# DAC_1_0.net
KiCad netlist of a schematic drawn in EAGLE
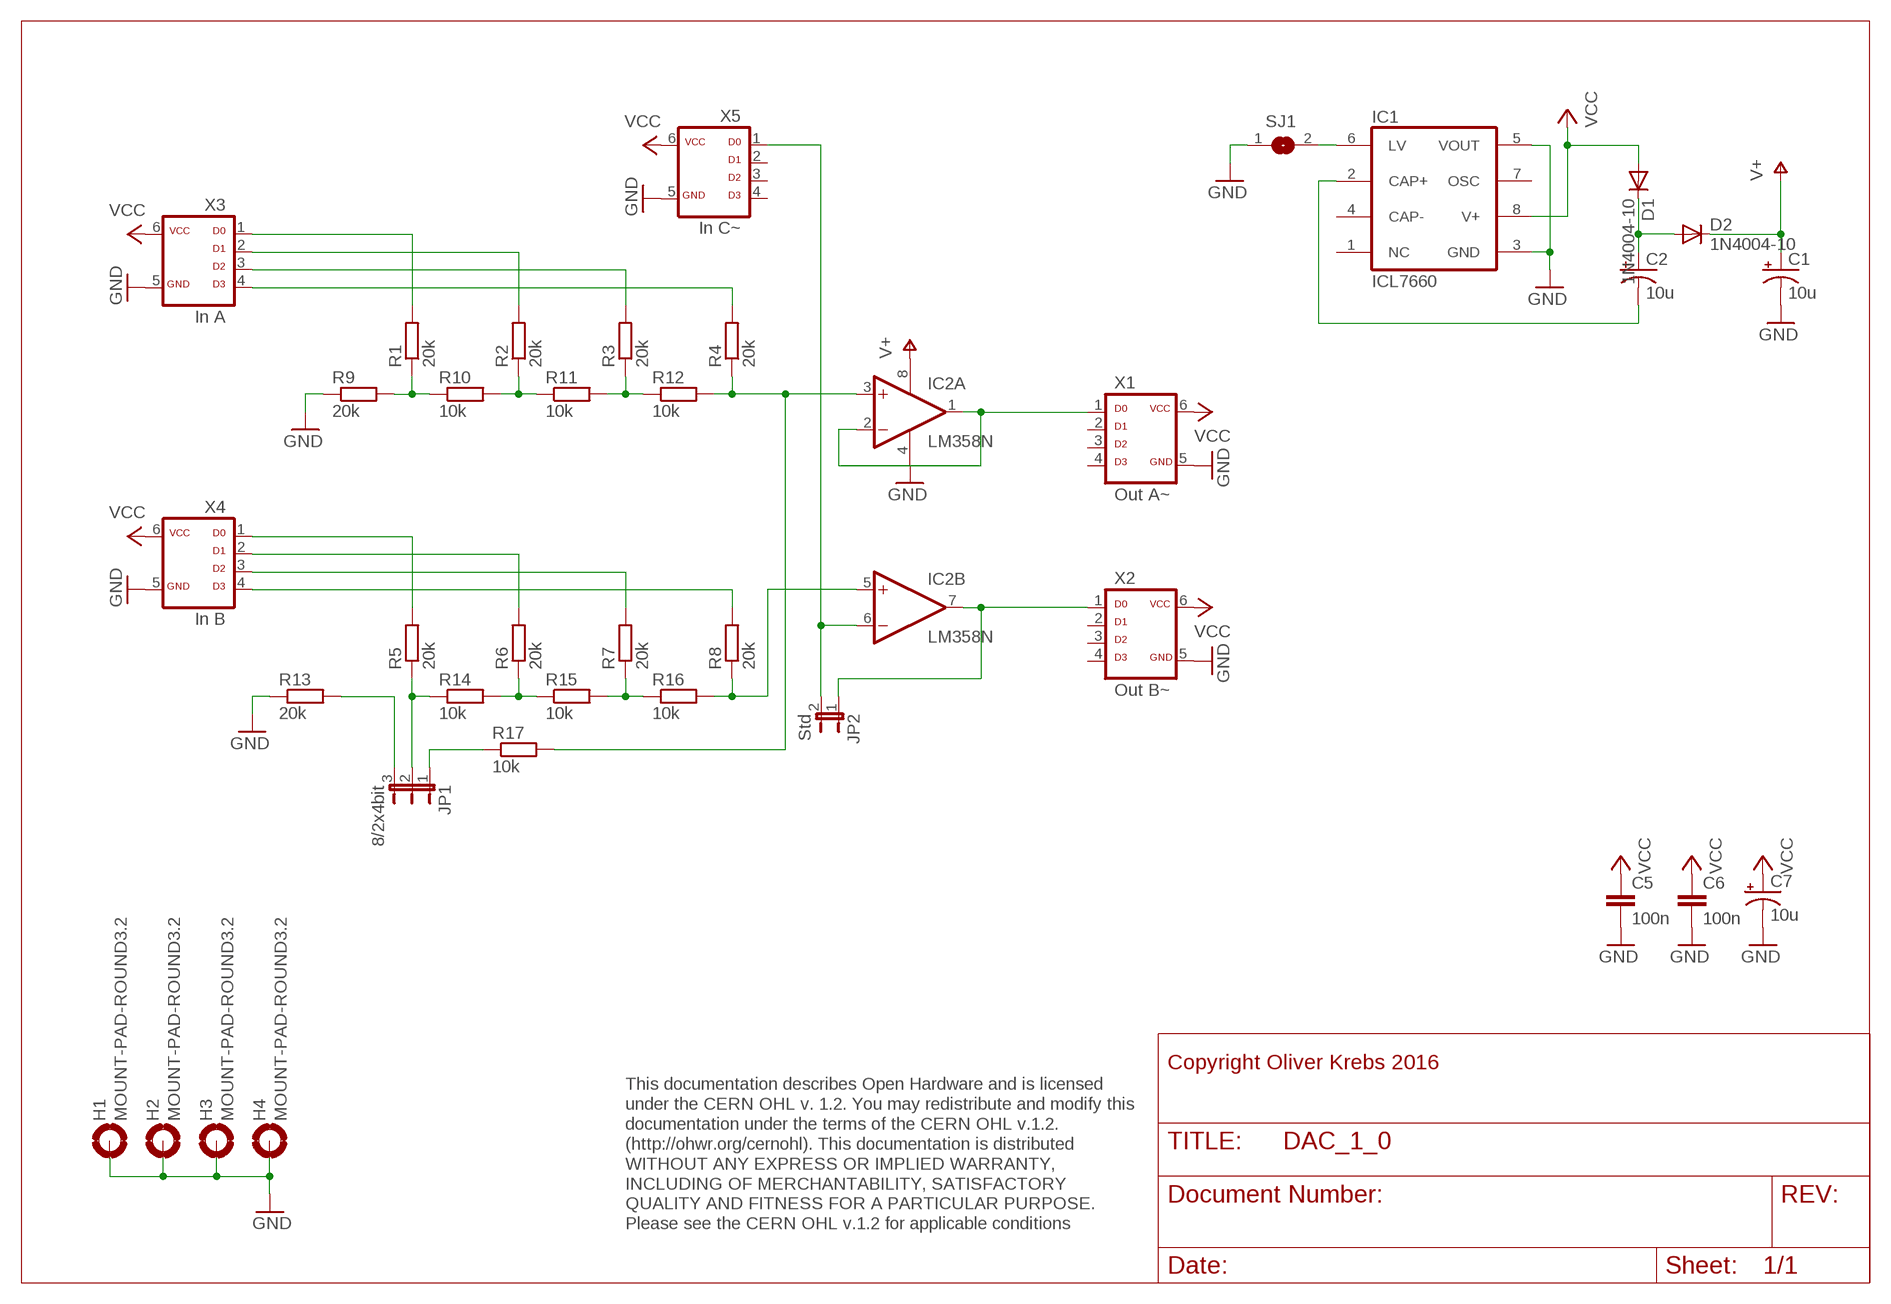
[diagram p0: schematic, sheet 1]

(export (version "E")
  (design (tool "Eeschema 10.0.6"))
  (components
    (comp (ref "C1")
      (value "10u")
      (footprint "eagle-import:CPOL-RADIAL-10UF-25V")
      (libsource (lib "eagle-import") (part "CAP_POLPTH2"))
    )
    (comp (ref "C2")
      (value "10u")
      (footprint "eagle-import:CPOL-RADIAL-10UF-25V")
      (libsource (lib "eagle-import") (part "CAP_POLPTH2"))
    )
    (comp (ref "C5")
      (value "100n")
      (footprint "eagle-import:CAP-PTH-5MM")
      (libsource (lib "eagle-import") (part "CAPPTH1"))
    )
    (comp (ref "C6")
      (value "100n")
      (footprint "eagle-import:CAP-PTH-5MM")
      (libsource (lib "eagle-import") (part "CAPPTH1"))
    )
    (comp (ref "C7")
      (value "10u")
      (footprint "eagle-import:CPOL-RADIAL-10UF-25V")
      (libsource (lib "eagle-import") (part "CAP_POLPTH2"))
    )
    (comp (ref "D1")
      (value "1N4004-10")
      (footprint "eagle-import:DO41-10")
      (libsource (lib "eagle-import") (part "1N4004-10"))
    )
    (comp (ref "D2")
      (value "1N4004-10")
      (footprint "eagle-import:DO41-10")
      (libsource (lib "eagle-import") (part "1N4004-10"))
    )
    (comp (ref "H1")
      (value "MOUNT-PAD-ROUND3.2")
      (footprint "eagle-import:3,2-PAD")
      (libsource (lib "eagle-import") (part "MOUNT-PAD-ROUND3.2"))
    )
    (comp (ref "H2")
      (value "MOUNT-PAD-ROUND3.2")
      (footprint "eagle-import:3,2-PAD")
      (libsource (lib "eagle-import") (part "MOUNT-PAD-ROUND3.2"))
    )
    (comp (ref "H3")
      (value "MOUNT-PAD-ROUND3.2")
      (footprint "eagle-import:3,2-PAD")
      (libsource (lib "eagle-import") (part "MOUNT-PAD-ROUND3.2"))
    )
    (comp (ref "H4")
      (value "MOUNT-PAD-ROUND3.2")
      (footprint "eagle-import:3,2-PAD")
      (libsource (lib "eagle-import") (part "MOUNT-PAD-ROUND3.2"))
    )
    (comp (ref "IC1")
      (value "ICL7660")
      (footprint "eagle-import:DIL08")
      (fields (field (name "MF") "INTERSIL") (field (name "MPN") "ICL7660CPA"))
      (libsource (lib "eagle-import") (part "ICL7660CPA"))
    )
    (comp (ref "IC2")
      (value "LM358N")
      (footprint "eagle-import:DIL08")
      (libsource (lib "eagle-import") (part "LM358N"))
    )
    (comp (ref "JP1")
      (value "8/2x4bit")
      (footprint "eagle-import:JP2-U")
      (libsource (lib "eagle-import") (part "JP2EJP2-U"))
    )
    (comp (ref "JP2")
      (value "Std")
      (footprint "eagle-import:JP1")
      (libsource (lib "eagle-import") (part "JP1E"))
    )
    (comp (ref "R1")
      (value "20k")
      (footprint "eagle-import:0207_2V")
      (libsource (lib "eagle-import") (part "R-EU_0207/2V"))
    )
    (comp (ref "R2")
      (value "20k")
      (footprint "eagle-import:0207_2V")
      (libsource (lib "eagle-import") (part "R-EU_0207/2V"))
    )
    (comp (ref "R3")
      (value "20k")
      (footprint "eagle-import:0207_2V")
      (libsource (lib "eagle-import") (part "R-EU_0207/2V"))
    )
    (comp (ref "R4")
      (value "20k")
      (footprint "eagle-import:0207_2V")
      (libsource (lib "eagle-import") (part "R-EU_0207/2V"))
    )
    (comp (ref "R5")
      (value "20k")
      (footprint "eagle-import:0207_2V")
      (libsource (lib "eagle-import") (part "R-EU_0207/2V"))
    )
    (comp (ref "R6")
      (value "20k")
      (footprint "eagle-import:0207_2V")
      (libsource (lib "eagle-import") (part "R-EU_0207/2V"))
    )
    (comp (ref "R7")
      (value "20k")
      (footprint "eagle-import:0207_2V")
      (libsource (lib "eagle-import") (part "R-EU_0207/2V"))
    )
    (comp (ref "R8")
      (value "20k")
      (footprint "eagle-import:0207_2V")
      (libsource (lib "eagle-import") (part "R-EU_0207/2V"))
    )
    (comp (ref "R9")
      (value "20k")
      (footprint "eagle-import:0207_2V")
      (libsource (lib "eagle-import") (part "R-EU_0207/2V"))
    )
    (comp (ref "R10")
      (value "10k")
      (footprint "eagle-import:0207_2V")
      (libsource (lib "eagle-import") (part "R-EU_0207/2V"))
    )
    (comp (ref "R11")
      (value "10k")
      (footprint "eagle-import:0207_2V")
      (libsource (lib "eagle-import") (part "R-EU_0207/2V"))
    )
    (comp (ref "R12")
      (value "10k")
      (footprint "eagle-import:0207_2V")
      (libsource (lib "eagle-import") (part "R-EU_0207/2V"))
    )
    (comp (ref "R13")
      (value "20k")
      (footprint "eagle-import:0207_2V")
      (libsource (lib "eagle-import") (part "R-EU_0207/2V"))
    )
    (comp (ref "R14")
      (value "10k")
      (footprint "eagle-import:0207_2V")
      (libsource (lib "eagle-import") (part "R-EU_0207/2V"))
    )
    (comp (ref "R15")
      (value "10k")
      (footprint "eagle-import:0207_2V")
      (libsource (lib "eagle-import") (part "R-EU_0207/2V"))
    )
    (comp (ref "R16")
      (value "10k")
      (footprint "eagle-import:0207_2V")
      (libsource (lib "eagle-import") (part "R-EU_0207/2V"))
    )
    (comp (ref "R17")
      (value "10k")
      (footprint "eagle-import:0207_2V")
      (libsource (lib "eagle-import") (part "R-EU_0207/2V"))
    )
    (comp (ref "SJ1") (value "SJ") (footprint "eagle-import:SJ") (libsource (lib "eagle-import") (part "SJ")))
    (comp (ref "X1")
      (value "Out A~")
      (footprint "eagle-import:ML-6")
      (libsource (lib "eagle-import") (part "ML6D"))
    )
    (comp (ref "X2")
      (value "Out B~")
      (footprint "eagle-import:ML-6")
      (libsource (lib "eagle-import") (part "ML6D"))
    )
    (comp (ref "X3")
      (value "In A")
      (footprint "eagle-import:ML-6")
      (libsource (lib "eagle-import") (part "ML6D"))
    )
    (comp (ref "X4")
      (value "In B")
      (footprint "eagle-import:ML-6")
      (libsource (lib "eagle-import") (part "ML6D"))
    )
    (comp (ref "X5")
      (value "In C~")
      (footprint "eagle-import:ML-6")
      (libsource (lib "eagle-import") (part "ML6D"))
    )
  )
  (nets
    (net (code "1") (name "GND") (class "Default")
      (node (ref "C1") (pin "2") (pinfunction "-_2") (pintype "passive"))
      (node (ref "C5") (pin "2") (pinfunction "2_2") (pintype "passive"))
      (node (ref "C6") (pin "2") (pinfunction "2_2") (pintype "passive"))
      (node (ref "C7") (pin "2") (pinfunction "-_2") (pintype "passive"))
      (node (ref "H1") (pin "B3,2") (pinfunction "MOUNT_B3,2") (pintype "passive"))
      (node (ref "H2") (pin "B3,2") (pinfunction "MOUNT_B3,2") (pintype "passive"))
      (node (ref "H3") (pin "B3,2") (pinfunction "MOUNT_B3,2") (pintype "passive"))
      (node (ref "H4") (pin "B3,2") (pinfunction "MOUNT_B3,2") (pintype "passive"))
      (node (ref "IC1") (pin "3") (pinfunction "GND_3") (pintype "power_in"))
      (node (ref "IC1") (pin "5") (pinfunction "VOUT_5") (pintype "output"))
      (node (ref "IC2") (pin "4") (pinfunction "V-_4") (pintype "power_in"))
      (node (ref "R13") (pin "1") (pinfunction "1_1") (pintype "passive"))
      (node (ref "R9") (pin "1") (pinfunction "1_1") (pintype "passive"))
      (node (ref "SJ1") (pin "1") (pinfunction "1_1") (pintype "passive"))
      (node (ref "X1") (pin "5") (pinfunction "5_5") (pintype "passive"))
      (node (ref "X2") (pin "5") (pinfunction "5_5") (pintype "passive"))
      (node (ref "X3") (pin "5") (pinfunction "5_5") (pintype "passive"))
      (node (ref "X4") (pin "5") (pinfunction "5_5") (pintype "passive"))
      (node (ref "X5") (pin "5") (pinfunction "5_5") (pintype "passive"))
    )
    (net (code "2") (name "Net-(C2-+)") (class "Default")
      (node (ref "C2") (pin "1") (pinfunction "+_1") (pintype "passive"))
      (node (ref "D1") (pin "C") (pinfunction "C_C") (pintype "passive"))
      (node (ref "D2") (pin "A") (pinfunction "A_A") (pintype "passive"))
    )
    (net (code "3") (name "Net-(C2--)") (class "Default")
      (node (ref "C2") (pin "2") (pinfunction "-_2") (pintype "passive"))
      (node (ref "IC1") (pin "2") (pinfunction "CAP+_2") (pintype "passive"))
    )
    (net (code "4") (name "Net-(IC1-LV)") (class "Default")
      (node (ref "IC1") (pin "6") (pinfunction "LV_6") (pintype "passive"))
      (node (ref "SJ1") (pin "2") (pinfunction "2_2") (pintype "passive"))
    )
    (net (code "5") (name "Net-(IC2A-+IN)") (class "Default")
      (node (ref "IC2") (pin "3") (pinfunction "+IN_3") (pintype "input"))
      (node (ref "R12") (pin "2") (pinfunction "2_2") (pintype "passive"))
      (node (ref "R17") (pin "2") (pinfunction "2_2") (pintype "passive"))
      (node (ref "R4") (pin "1") (pinfunction "1_1") (pintype "passive"))
    )
    (net (code "6") (name "Net-(IC2A--IN)") (class "Default")
      (node (ref "IC2") (pin "1") (pinfunction "OUT_1") (pintype "output"))
      (node (ref "IC2") (pin "2") (pinfunction "-IN_2") (pintype "input"))
      (node (ref "X1") (pin "1") (pinfunction "1_1") (pintype "passive"))
    )
    (net (code "7") (name "Net-(IC2B-+IN)") (class "Default")
      (node (ref "IC2") (pin "5") (pinfunction "+IN_5") (pintype "input"))
      (node (ref "R16") (pin "2") (pinfunction "2_2") (pintype "passive"))
      (node (ref "R8") (pin "1") (pinfunction "1_1") (pintype "passive"))
    )
    (net (code "8") (name "Net-(IC2B--IN)") (class "Default")
      (node (ref "IC2") (pin "6") (pinfunction "-IN_6") (pintype "input"))
      (node (ref "JP2") (pin "2") (pinfunction "2_2") (pintype "passive"))
      (node (ref "X5") (pin "1") (pinfunction "1_1") (pintype "passive"))
    )
    (net (code "9") (name "Net-(IC2B-OUT)") (class "Default")
      (node (ref "IC2") (pin "7") (pinfunction "OUT_7") (pintype "output"))
      (node (ref "JP2") (pin "1") (pinfunction "1_1") (pintype "passive"))
      (node (ref "X2") (pin "1") (pinfunction "1_1") (pintype "passive"))
    )
    (net (code "10") (name "Net-(JP1-Pad1)") (class "Default")
      (node (ref "JP1") (pin "1") (pinfunction "1_1") (pintype "passive"))
      (node (ref "R17") (pin "1") (pinfunction "1_1") (pintype "passive"))
    )
    (net (code "11") (name "Net-(JP1-Pad2)") (class "Default")
      (node (ref "JP1") (pin "2") (pinfunction "2_2") (pintype "passive"))
      (node (ref "R14") (pin "1") (pinfunction "1_1") (pintype "passive"))
      (node (ref "R5") (pin "1") (pinfunction "1_1") (pintype "passive"))
    )
    (net (code "12") (name "Net-(JP1-Pad3)") (class "Default")
      (node (ref "JP1") (pin "3") (pinfunction "3_3") (pintype "passive"))
      (node (ref "R13") (pin "2") (pinfunction "2_2") (pintype "passive"))
    )
    (net (code "13") (name "Net-(R1-Pad1)") (class "Default")
      (node (ref "R1") (pin "1") (pinfunction "1_1") (pintype "passive"))
      (node (ref "R10") (pin "1") (pinfunction "1_1") (pintype "passive"))
      (node (ref "R9") (pin "2") (pinfunction "2_2") (pintype "passive"))
    )
    (net (code "14") (name "Net-(R1-Pad2)") (class "Default")
      (node (ref "R1") (pin "2") (pinfunction "2_2") (pintype "passive"))
      (node (ref "X3") (pin "1") (pinfunction "1_1") (pintype "passive"))
    )
    (net (code "15") (name "Net-(R2-Pad2)") (class "Default")
      (node (ref "R2") (pin "2") (pinfunction "2_2") (pintype "passive"))
      (node (ref "X3") (pin "2") (pinfunction "2_2") (pintype "passive"))
    )
    (net (code "16") (name "Net-(R3-Pad2)") (class "Default")
      (node (ref "R3") (pin "2") (pinfunction "2_2") (pintype "passive"))
      (node (ref "X3") (pin "3") (pinfunction "3_3") (pintype "passive"))
    )
    (net (code "17") (name "Net-(R4-Pad2)") (class "Default")
      (node (ref "R4") (pin "2") (pinfunction "2_2") (pintype "passive"))
      (node (ref "X3") (pin "4") (pinfunction "4_4") (pintype "passive"))
    )
    (net (code "18") (name "Net-(R5-Pad2)") (class "Default")
      (node (ref "R5") (pin "2") (pinfunction "2_2") (pintype "passive"))
      (node (ref "X4") (pin "1") (pinfunction "1_1") (pintype "passive"))
    )
    (net (code "19") (name "Net-(R6-Pad2)") (class "Default")
      (node (ref "R6") (pin "2") (pinfunction "2_2") (pintype "passive"))
      (node (ref "X4") (pin "2") (pinfunction "2_2") (pintype "passive"))
    )
    (net (code "20") (name "Net-(R7-Pad2)") (class "Default")
      (node (ref "R7") (pin "2") (pinfunction "2_2") (pintype "passive"))
      (node (ref "X4") (pin "3") (pinfunction "3_3") (pintype "passive"))
    )
    (net (code "21") (name "Net-(R8-Pad2)") (class "Default")
      (node (ref "R8") (pin "2") (pinfunction "2_2") (pintype "passive"))
      (node (ref "X4") (pin "4") (pinfunction "4_4") (pintype "passive"))
    )
    (net (code "22") (name "Net-(R10-Pad2)") (class "Default")
      (node (ref "R10") (pin "2") (pinfunction "2_2") (pintype "passive"))
      (node (ref "R11") (pin "1") (pinfunction "1_1") (pintype "passive"))
      (node (ref "R2") (pin "1") (pinfunction "1_1") (pintype "passive"))
    )
    (net (code "23") (name "Net-(R11-Pad2)") (class "Default")
      (node (ref "R11") (pin "2") (pinfunction "2_2") (pintype "passive"))
      (node (ref "R12") (pin "1") (pinfunction "1_1") (pintype "passive"))
      (node (ref "R3") (pin "1") (pinfunction "1_1") (pintype "passive"))
    )
    (net (code "24") (name "Net-(R14-Pad2)") (class "Default")
      (node (ref "R14") (pin "2") (pinfunction "2_2") (pintype "passive"))
      (node (ref "R15") (pin "1") (pinfunction "1_1") (pintype "passive"))
      (node (ref "R6") (pin "1") (pinfunction "1_1") (pintype "passive"))
    )
    (net (code "25") (name "Net-(R15-Pad2)") (class "Default")
      (node (ref "R15") (pin "2") (pinfunction "2_2") (pintype "passive"))
      (node (ref "R16") (pin "1") (pinfunction "1_1") (pintype "passive"))
      (node (ref "R7") (pin "1") (pinfunction "1_1") (pintype "passive"))
    )
    (net (code "26") (name "V+") (class "Default")
      (node (ref "C1") (pin "1") (pinfunction "+_1") (pintype "passive"))
      (node (ref "D2") (pin "C") (pinfunction "C_C") (pintype "passive"))
      (node (ref "IC2") (pin "8") (pinfunction "V+_8") (pintype "power_in"))
    )
    (net (code "27") (name "VCC") (class "Default")
      (node (ref "C5") (pin "1") (pinfunction "1_1") (pintype "passive"))
      (node (ref "C6") (pin "1") (pinfunction "1_1") (pintype "passive"))
      (node (ref "C7") (pin "1") (pinfunction "+_1") (pintype "passive"))
      (node (ref "D1") (pin "A") (pinfunction "A_A") (pintype "passive"))
      (node (ref "IC1") (pin "8") (pinfunction "V+_8") (pintype "power_in"))
      (node (ref "X1") (pin "6") (pinfunction "6_6") (pintype "passive"))
      (node (ref "X2") (pin "6") (pinfunction "6_6") (pintype "passive"))
      (node (ref "X3") (pin "6") (pinfunction "6_6") (pintype "passive"))
      (node (ref "X4") (pin "6") (pinfunction "6_6") (pintype "passive"))
      (node (ref "X5") (pin "6") (pinfunction "6_6") (pintype "passive"))
    )
    (net (code "28") (name "unconnected-(IC1-CAP--Pad4)") (class "Default")
      (node (ref "IC1") (pin "4") (pinfunction "CAP-_4") (pintype "passive"))
    )
    (net (code "29") (name "unconnected-(IC1-NC-Pad1)") (class "Default")
      (node (ref "IC1") (pin "1") (pinfunction "NC_1") (pintype "no_connect"))
    )
    (net (code "30") (name "unconnected-(IC1-OSC-Pad7)") (class "Default")
      (node (ref "IC1") (pin "7") (pinfunction "OSC_7") (pintype "output"))
    )
    (net (code "31") (name "unconnected-(X1-Pad2)") (class "Default")
      (node (ref "X1") (pin "2") (pinfunction "2_2") (pintype "passive"))
    )
    (net (code "32") (name "unconnected-(X1-Pad3)") (class "Default")
      (node (ref "X1") (pin "3") (pinfunction "3_3") (pintype "passive"))
    )
    (net (code "33") (name "unconnected-(X1-Pad4)") (class "Default")
      (node (ref "X1") (pin "4") (pinfunction "4_4") (pintype "passive"))
    )
    (net (code "34") (name "unconnected-(X2-Pad2)") (class "Default")
      (node (ref "X2") (pin "2") (pinfunction "2_2") (pintype "passive"))
    )
    (net (code "35") (name "unconnected-(X2-Pad3)") (class "Default")
      (node (ref "X2") (pin "3") (pinfunction "3_3") (pintype "passive"))
    )
    (net (code "36") (name "unconnected-(X2-Pad4)") (class "Default")
      (node (ref "X2") (pin "4") (pinfunction "4_4") (pintype "passive"))
    )
    (net (code "37") (name "unconnected-(X5-Pad2)") (class "Default")
      (node (ref "X5") (pin "2") (pinfunction "2_2") (pintype "passive"))
    )
    (net (code "38") (name "unconnected-(X5-Pad3)") (class "Default")
      (node (ref "X5") (pin "3") (pinfunction "3_3") (pintype "passive"))
    )
    (net (code "39") (name "unconnected-(X5-Pad4)") (class "Default")
      (node (ref "X5") (pin "4") (pinfunction "4_4") (pintype "passive"))
    )
  )
)
